# Sheet1.net
KiCad netlist of a schematic drawn in Altium Designer
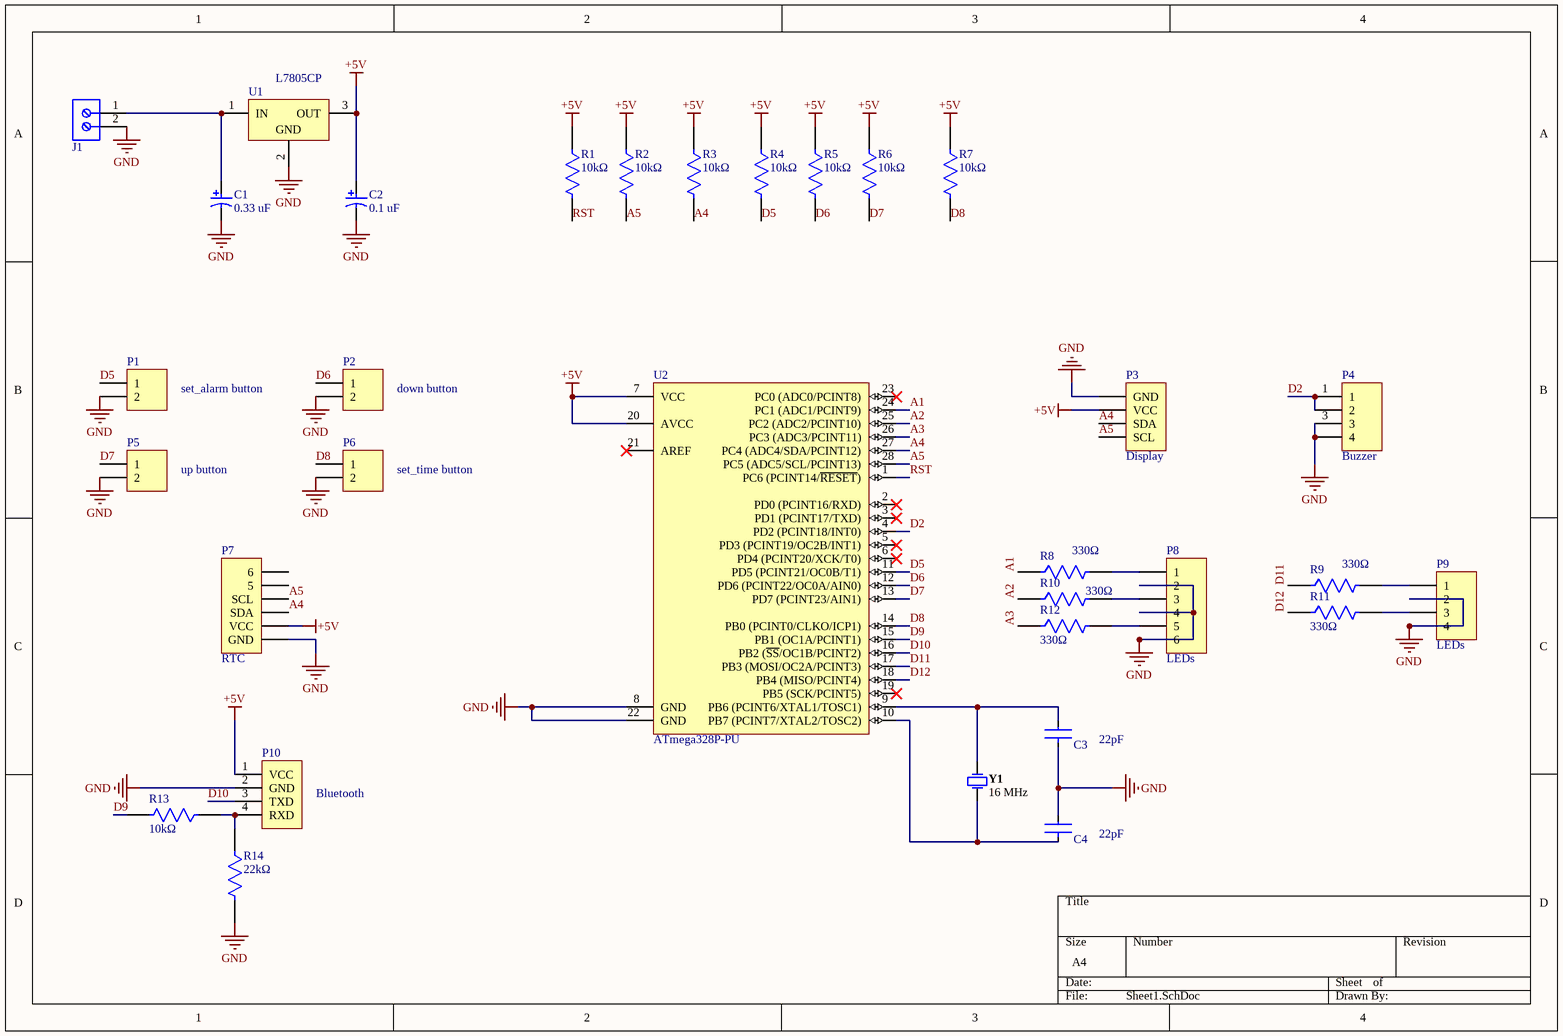
[diagram p0: Sheet1.SchDoc]

(export (version "E")
  (design (tool "Eeschema 10.0.6"))
  (components
    (comp (ref "C1")
      (value "PLF1A471MDO1_big")
      (footprint "NIC-PLF-10x13-2_V")
      (description "Aluminum Electrolytic Capacitor, 470 uF +/-20%, 10 V, -55 to 105 degC, 2-Pin THD, RoHS")
      (fields
        (field (name "RATED CAPACITANCE") "0.33 uF")
        (field (name "MANUFACTURER") "Nichicon")
        (field (name "PARTNUMBER") "PLF1A471MDO1")
      )
      (libsource (lib "Altium Content Vault") (part "NIC-CAP-P-2"))
    )
    (comp (ref "C2")
      (value "PLF1A471MDO1_big")
      (footprint "NIC-PLF-10x13-2_V")
      (description "Aluminum Electrolytic Capacitor, 470 uF +/-20%, 10 V, -55 to 105 degC, 2-Pin THD, RoHS")
      (fields
        (field (name "RATED CAPACITANCE") "0.1 uF")
        (field (name "MANUFACTURER") "Nichicon")
        (field (name "PARTNUMBER") "PLF1A471MDO1")
      )
      (libsource (lib "Altium Content Vault") (part "NIC-CAP-P-2"))
    )
    (comp (ref "C3")
      (value "RDE5C1H220J0K1H03B")
      (footprint "FP-RDE0M1-MFG")
      (description "Ceramic Capacitor 22pF ±5% 50V C0G Radial")
      (fields (field (name "CAPACITANCE") "22pF") (field (name "TOLERANCE") "5%"))
      (libsource (lib "Altium Content Vault") (part "b4654b650e69147ec39a6b967a45e02"))
    )
    (comp (ref "C4")
      (value "RDE5C1H220J0K1H03B")
      (footprint "FP-RDE0M1-MFG")
      (description "Ceramic Capacitor 22pF ±5% 50V C0G Radial")
      (fields (field (name "CAPACITANCE") "22pF") (field (name "TOLERANCE") "5%"))
      (libsource (lib "Altium Content Vault") (part "b4654b650e69147ec39a6b967a45e02"))
    )
    (comp (ref "J1")
      (value "691102710002")
      (footprint "691102710002")
      (description "Series 102 - 5.00 mm Horizontal Entry Modular with Pressure Clamp WR-TBL, 2 pin")
      (fields (field (name "MANUFACTURER") "Wurth Elektronik") (field (name "PUBLISHER") "WurthElektronik"))
      (libsource (lib "Altium Content Vault") (part "WE-CN-1P-F-TB2"))
    )
    (comp (ref "P1")
      (value "set_alarm button")
      (footprint "HDR1X2")
      (description "Header, 2-Pin")
      (fields (field (name "PUBLISHER") "Altium Limited"))
      (libsource (lib "Miscellaneous Connectors") (part "Header 2"))
    )
    (comp (ref "P2")
      (value "down button")
      (footprint "HDR1X2")
      (description "Header, 2-Pin")
      (fields (field (name "PUBLISHER") "Altium Limited"))
      (libsource (lib "Miscellaneous Connectors") (part "Header 2"))
    )
    (comp (ref "P3")
      (value "Display")
      (footprint "HDR1X4")
      (description "Header, 4-Pin")
      (fields (field (name "PUBLISHER") "Altium Limited"))
      (libsource (lib "Miscellaneous Connectors") (part "Header 4"))
    )
    (comp (ref "P4")
      (value "Buzzer")
      (footprint "HDR1X4")
      (description "Header, 4-Pin")
      (fields (field (name "PUBLISHER") "Altium Limited"))
      (libsource (lib "") (part "Header 4_2"))
    )
    (comp (ref "P5")
      (value "up button")
      (footprint "HDR1X2")
      (description "Header, 2-Pin")
      (fields (field (name "PUBLISHER") "Altium Limited"))
      (libsource (lib "Miscellaneous Connectors") (part "Header 2"))
    )
    (comp (ref "P6")
      (value "set_time button")
      (footprint "HDR1X2")
      (description "Header, 2-Pin")
      (fields (field (name "PUBLISHER") "Altium Limited"))
      (libsource (lib "Miscellaneous Connectors") (part "Header 2"))
    )
    (comp (ref "P7")
      (value "RTC")
      (footprint "HDR1X6")
      (description "Header, 6-Pin")
      (fields (field (name "PUBLISHER") "Altium Limited"))
      (libsource (lib "") (part "Header 6_1"))
    )
    (comp (ref "P8")
      (value "LEDs")
      (footprint "HDR1X6")
      (description "Header, 6-Pin")
      (fields (field (name "PUBLISHER") "Altium Limited"))
      (libsource (lib "Miscellaneous Connectors") (part "Header 6"))
    )
    (comp (ref "P9")
      (value "LEDs")
      (footprint "HDR1X4")
      (description "Header, 4-Pin")
      (fields (field (name "PUBLISHER") "Altium Limited"))
      (libsource (lib "Miscellaneous Connectors") (part "Header 4"))
    )
    (comp (ref "P10")
      (value "Bluetooth")
      (footprint "HDR1X4")
      (description "Header, 4-Pin")
      (fields (field (name "PUBLISHER") "Altium Limited"))
      (libsource (lib "") (part "Header 4_1"))
    )
    (comp (ref "R1")
      (value "MFR-25FBF52-1K18")
      (footprint "FP-MFR-25-MFG")
      (description "RES 1.18K OHM 1/4W 1% AXIAL")
      (fields
        (field (name "MANUFACTURER") "Yageo")
        (field (name "TOLERANCE") "1%")
        (field (name "RESISTANCE") "10kΩ")
      )
      (libsource (lib "Altium Content Vault") (part "1029c3af85768c4190bb7ad29bc67b5"))
    )
    (comp (ref "R2")
      (value "MFR-25FBF52-1K18")
      (footprint "FP-MFR-25-MFG")
      (description "RES 1.18K OHM 1/4W 1% AXIAL")
      (fields
        (field (name "MANUFACTURER") "Yageo")
        (field (name "TOLERANCE") "1%")
        (field (name "RESISTANCE") "10kΩ")
      )
      (libsource (lib "Altium Content Vault") (part "1029c3af85768c4190bb7ad29bc67b5"))
    )
    (comp (ref "R3")
      (value "MFR-25FBF52-1K18")
      (footprint "FP-MFR-25-MFG")
      (description "RES 1.18K OHM 1/4W 1% AXIAL")
      (fields
        (field (name "MANUFACTURER") "Yageo")
        (field (name "TOLERANCE") "1%")
        (field (name "RESISTANCE") "10kΩ")
      )
      (libsource (lib "Altium Content Vault") (part "1029c3af85768c4190bb7ad29bc67b5"))
    )
    (comp (ref "R4")
      (value "MFR-25FBF52-1K18")
      (footprint "FP-MFR-25-MFG")
      (description "RES 1.18K OHM 1/4W 1% AXIAL")
      (fields
        (field (name "MANUFACTURER") "Yageo")
        (field (name "TOLERANCE") "1%")
        (field (name "RESISTANCE") "10kΩ")
      )
      (libsource (lib "Altium Content Vault") (part "1029c3af85768c4190bb7ad29bc67b5"))
    )
    (comp (ref "R5")
      (value "MFR-25FBF52-1K18")
      (footprint "FP-MFR-25-MFG")
      (description "RES 1.18K OHM 1/4W 1% AXIAL")
      (fields
        (field (name "MANUFACTURER") "Yageo")
        (field (name "TOLERANCE") "1%")
        (field (name "RESISTANCE") "10kΩ")
      )
      (libsource (lib "Altium Content Vault") (part "1029c3af85768c4190bb7ad29bc67b5"))
    )
    (comp (ref "R6")
      (value "MFR-25FBF52-1K18")
      (footprint "FP-MFR-25-MFG")
      (description "RES 1.18K OHM 1/4W 1% AXIAL")
      (fields
        (field (name "MANUFACTURER") "Yageo")
        (field (name "TOLERANCE") "1%")
        (field (name "RESISTANCE") "10kΩ")
      )
      (libsource (lib "Altium Content Vault") (part "1029c3af85768c4190bb7ad29bc67b5"))
    )
    (comp (ref "R7")
      (value "MFR-25FBF52-1K18")
      (footprint "FP-MFR-25-MFG")
      (description "RES 1.18K OHM 1/4W 1% AXIAL")
      (fields
        (field (name "MANUFACTURER") "Yageo")
        (field (name "TOLERANCE") "1%")
        (field (name "RESISTANCE") "10kΩ")
      )
      (libsource (lib "Altium Content Vault") (part "1029c3af85768c4190bb7ad29bc67b5"))
    )
    (comp (ref "R8")
      (value "MFR-25FBF52-1K18")
      (footprint "FP-MFR-25-MFG")
      (description "RES 1.18K OHM 1/4W 1% AXIAL")
      (fields
        (field (name "MANUFACTURER") "Yageo")
        (field (name "TOLERANCE") "1%")
        (field (name "RESISTANCE") "330Ω")
      )
      (libsource (lib "Altium Content Vault") (part "1029c3af85768c4190bb7ad29bc67b5"))
    )
    (comp (ref "R9")
      (value "MFR-25FBF52-1K18")
      (footprint "FP-MFR-25-MFG")
      (description "RES 1.18K OHM 1/4W 1% AXIAL")
      (fields
        (field (name "MANUFACTURER") "Yageo")
        (field (name "TOLERANCE") "1%")
        (field (name "RESISTANCE") "330Ω")
      )
      (libsource (lib "Altium Content Vault") (part "1029c3af85768c4190bb7ad29bc67b5"))
    )
    (comp (ref "R10")
      (value "MFR-25FBF52-1K18")
      (footprint "FP-MFR-25-MFG")
      (description "RES 1.18K OHM 1/4W 1% AXIAL")
      (fields
        (field (name "MANUFACTURER") "Yageo")
        (field (name "TOLERANCE") "1%")
        (field (name "RESISTANCE") "330Ω")
      )
      (libsource (lib "Altium Content Vault") (part "1029c3af85768c4190bb7ad29bc67b5"))
    )
    (comp (ref "R11")
      (value "MFR-25FBF52-1K18")
      (footprint "FP-MFR-25-MFG")
      (description "RES 1.18K OHM 1/4W 1% AXIAL")
      (fields
        (field (name "MANUFACTURER") "Yageo")
        (field (name "TOLERANCE") "1%")
        (field (name "RESISTANCE") "330Ω")
      )
      (libsource (lib "Altium Content Vault") (part "1029c3af85768c4190bb7ad29bc67b5"))
    )
    (comp (ref "R12")
      (value "MFR-25FBF52-1K18")
      (footprint "FP-MFR-25-MFG")
      (description "RES 1.18K OHM 1/4W 1% AXIAL")
      (fields
        (field (name "MANUFACTURER") "Yageo")
        (field (name "TOLERANCE") "1%")
        (field (name "RESISTANCE") "330Ω")
      )
      (libsource (lib "Altium Content Vault") (part "1029c3af85768c4190bb7ad29bc67b5"))
    )
    (comp (ref "R13")
      (value "MFR-25FBF52-1K18")
      (footprint "FP-MFR-25-MFG")
      (description "RES 1.18K OHM 1/4W 1% AXIAL")
      (fields
        (field (name "MANUFACTURER") "Yageo")
        (field (name "TOLERANCE") "1%")
        (field (name "RESISTANCE") "10kΩ")
      )
      (libsource (lib "Altium Content Vault") (part "1029c3af85768c4190bb7ad29bc67b5"))
    )
    (comp (ref "R14")
      (value "MFR-25FBF52-1K18")
      (footprint "FP-MFR-25-MFG")
      (description "RES 1.18K OHM 1/4W 1% AXIAL")
      (fields
        (field (name "MANUFACTURER") "Yageo")
        (field (name "TOLERANCE") "1%")
        (field (name "RESISTANCE") "22kΩ")
      )
      (libsource (lib "Altium Content Vault") (part "1029c3af85768c4190bb7ad29bc67b5"))
    )
    (comp (ref "U1")
      (value "L7805CP")
      (footprint "TO220FP")
      (description "Positive Voltage Regulator, 5V, 3-Pin TO-220FP")
      (libsource (lib "Altium Content Vault") (part "PM-REG-L4940-SIL3"))
    )
    (comp (ref "U2")
      (value "ATmega328P-PU")
      (footprint "28P3")
      (libsource (lib "Altium Content Vault") (part "MC-8B-ATM48-IL28"))
    )
    (comp (ref "Y1")
      (value "16 MHz")
      (footprint "FOX-FOXSLF160-20")
      (description "Resistance Weld Thru-Hole Crystal, 16 MHz, -20 to 70 degC, 2-Pin THD, RoHS, Bulk")
      (fields (field (name "TOLERANCE") "1%"))
      (libsource (lib "Altium Content Vault") (part "XTAL-1-2-2"))
    )
  )
  (nets
    (net (code "1") (name "+5V") (class "Default")
      (node (ref "C2") (pin "1") (pinfunction "1_1") (pintype "passive"))
      (node (ref "P10") (pin "1") (pinfunction "VCC_1") (pintype "passive"))
      (node (ref "P3") (pin "2") (pinfunction "VCC_2") (pintype "passive"))
      (node (ref "P7") (pin "2") (pinfunction "VCC_2") (pintype "passive"))
      (node (ref "R1") (pin "1") (pinfunction "1_1") (pintype "passive"))
      (node (ref "R2") (pin "1") (pinfunction "1_1") (pintype "passive"))
      (node (ref "R3") (pin "1") (pinfunction "1_1") (pintype "passive"))
      (node (ref "R4") (pin "1") (pinfunction "1_1") (pintype "passive"))
      (node (ref "R5") (pin "1") (pinfunction "1_1") (pintype "passive"))
      (node (ref "R6") (pin "1") (pinfunction "1_1") (pintype "passive"))
      (node (ref "R7") (pin "1") (pinfunction "1_1") (pintype "passive"))
      (node (ref "U1") (pin "3") (pinfunction "OUT_3") (pintype "power_in"))
      (node (ref "U2") (pin "20") (pinfunction "AVCC_20") (pintype "power_in"))
      (node (ref "U2") (pin "7") (pinfunction "VCC_7") (pintype "power_in"))
    )
    (net (code "2") (name "/A1") (class "Default")
      (node (ref "R8") (pin "1") (pinfunction "1_1") (pintype "passive"))
      (node (ref "U2") (pin "24") (pinfunction "PC1_(ADC1/PCINT9)_24") (pintype "bidirectional"))
    )
    (net (code "3") (name "/A2") (class "Default")
      (node (ref "R10") (pin "1") (pinfunction "1_1") (pintype "passive"))
      (node (ref "U2") (pin "25") (pinfunction "PC2_(ADC2/PCINT10)_25") (pintype "bidirectional"))
    )
    (net (code "4") (name "/A3") (class "Default")
      (node (ref "R12") (pin "1") (pinfunction "1_1") (pintype "passive"))
      (node (ref "U2") (pin "26") (pinfunction "PC3_(ADC3/PCINT11)_26") (pintype "bidirectional"))
    )
    (net (code "5") (name "/A4") (class "Default")
      (node (ref "P3") (pin "3") (pinfunction "SDA_3") (pintype "passive"))
      (node (ref "P7") (pin "3") (pinfunction "SDA_3") (pintype "passive"))
      (node (ref "R3") (pin "2") (pinfunction "2_2") (pintype "passive"))
      (node (ref "U2") (pin "27") (pinfunction "PC4_(ADC4/SDA/PCINT12)_27") (pintype "bidirectional"))
    )
    (net (code "6") (name "/A5") (class "Default")
      (node (ref "P3") (pin "4") (pinfunction "SCL_4") (pintype "passive"))
      (node (ref "P7") (pin "4") (pinfunction "SCL_4") (pintype "passive"))
      (node (ref "R2") (pin "2") (pinfunction "2_2") (pintype "passive"))
      (node (ref "U2") (pin "28") (pinfunction "PC5_(ADC5/SCL/PCINT13)_28") (pintype "bidirectional"))
    )
    (net (code "7") (name "/D2") (class "Default")
      (node (ref "P4") (pin "1") (pinfunction "1_1") (pintype "passive"))
      (node (ref "P4") (pin "2") (pinfunction "2_2") (pintype "passive"))
      (node (ref "U2") (pin "4") (pinfunction "PD2_(PCINT18/INT0)_4") (pintype "bidirectional"))
    )
    (net (code "8") (name "/D5") (class "Default")
      (node (ref "P1") (pin "1") (pinfunction "1_1") (pintype "passive"))
      (node (ref "R4") (pin "2") (pinfunction "2_2") (pintype "passive"))
      (node (ref "U2") (pin "11") (pinfunction "PD5_(PCINT21/OC0B/T1)_11") (pintype "bidirectional"))
    )
    (net (code "9") (name "/D6") (class "Default")
      (node (ref "P2") (pin "1") (pinfunction "1_1") (pintype "passive"))
      (node (ref "R5") (pin "2") (pinfunction "2_2") (pintype "passive"))
      (node (ref "U2") (pin "12") (pinfunction "PD6_(PCINT22/OC0A/AIN0)_12") (pintype "bidirectional"))
    )
    (net (code "10") (name "/D7") (class "Default")
      (node (ref "P5") (pin "1") (pinfunction "1_1") (pintype "passive"))
      (node (ref "R6") (pin "2") (pinfunction "2_2") (pintype "passive"))
      (node (ref "U2") (pin "13") (pinfunction "PD7_(PCINT23/AIN1)_13") (pintype "bidirectional"))
    )
    (net (code "11") (name "/D8") (class "Default")
      (node (ref "P6") (pin "1") (pinfunction "1_1") (pintype "passive"))
      (node (ref "R7") (pin "2") (pinfunction "2_2") (pintype "passive"))
      (node (ref "U2") (pin "14") (pinfunction "PB0_(PCINT0/CLKO/ICP1)_14") (pintype "bidirectional"))
    )
    (net (code "12") (name "/D9") (class "Default")
      (node (ref "R13") (pin "2") (pinfunction "2_2") (pintype "passive"))
      (node (ref "U2") (pin "15") (pinfunction "PB1_(OC1A/PCINT1)_15") (pintype "bidirectional"))
    )
    (net (code "13") (name "/D10") (class "Default")
      (node (ref "P10") (pin "3") (pinfunction "TXD_3") (pintype "passive"))
      (node (ref "U2") (pin "16") (pinfunction "PB2_(~{SS}/OC1B/PCINT2)_16") (pintype "bidirectional"))
    )
    (net (code "14") (name "/D11") (class "Default")
      (node (ref "R9") (pin "1") (pinfunction "1_1") (pintype "passive"))
      (node (ref "U2") (pin "17") (pinfunction "PB3_(MOSI/OC2A/PCINT3)_17") (pintype "bidirectional"))
    )
    (net (code "15") (name "/D12") (class "Default")
      (node (ref "R11") (pin "1") (pinfunction "1_1") (pintype "passive"))
      (node (ref "U2") (pin "18") (pinfunction "PB4_(MISO/PCINT4)_18") (pintype "bidirectional"))
    )
    (net (code "16") (name "/RST") (class "Default")
      (node (ref "R1") (pin "2") (pinfunction "2_2") (pintype "passive"))
      (node (ref "U2") (pin "1") (pinfunction "PC6_(PCINT14/~{RESET})_1") (pintype "bidirectional"))
    )
    (net (code "17") (name "GND") (class "Default")
      (node (ref "C1") (pin "2") (pinfunction "2_2") (pintype "passive"))
      (node (ref "C2") (pin "2") (pinfunction "2_2") (pintype "passive"))
      (node (ref "C3") (pin "1") (pinfunction "1_1") (pintype "passive"))
      (node (ref "C4") (pin "2") (pinfunction "2_2") (pintype "passive"))
      (node (ref "J1") (pin "2") (pinfunction "2_2") (pintype "passive"))
      (node (ref "P1") (pin "2") (pinfunction "2_2") (pintype "passive"))
      (node (ref "P10") (pin "2") (pinfunction "GND_2") (pintype "passive"))
      (node (ref "P2") (pin "2") (pinfunction "2_2") (pintype "passive"))
      (node (ref "P3") (pin "1") (pinfunction "GND_1") (pintype "passive"))
      (node (ref "P4") (pin "3") (pinfunction "3_3") (pintype "passive"))
      (node (ref "P4") (pin "4") (pinfunction "4_4") (pintype "passive"))
      (node (ref "P5") (pin "2") (pinfunction "2_2") (pintype "passive"))
      (node (ref "P6") (pin "2") (pinfunction "2_2") (pintype "passive"))
      (node (ref "P7") (pin "1") (pinfunction "GND_1") (pintype "passive"))
      (node (ref "P8") (pin "2") (pinfunction "2_2") (pintype "passive"))
      (node (ref "P8") (pin "4") (pinfunction "4_4") (pintype "passive"))
      (node (ref "P8") (pin "6") (pinfunction "6_6") (pintype "passive"))
      (node (ref "P9") (pin "2") (pinfunction "VCC_2") (pintype "passive"))
      (node (ref "P9") (pin "4") (pinfunction "SCL_4") (pintype "passive"))
      (node (ref "R14") (pin "2") (pinfunction "2_2") (pintype "passive"))
      (node (ref "U1") (pin "2") (pinfunction "GND_2") (pintype "power_in"))
      (node (ref "U2") (pin "22") (pinfunction "GND_22") (pintype "power_in"))
      (node (ref "U2") (pin "8") (pinfunction "GND_8") (pintype "power_in"))
    )
    (net (code "18") (name "Net-(P8-Pad1)") (class "Default")
      (node (ref "P8") (pin "1") (pinfunction "1_1") (pintype "passive"))
      (node (ref "R8") (pin "2") (pinfunction "2_2") (pintype "passive"))
    )
    (net (code "19") (name "Net-(P8-Pad3)") (class "Default")
      (node (ref "P8") (pin "3") (pinfunction "3_3") (pintype "passive"))
      (node (ref "R10") (pin "2") (pinfunction "2_2") (pintype "passive"))
    )
    (net (code "20") (name "Net-(P8-Pad5)") (class "Default")
      (node (ref "P8") (pin "5") (pinfunction "5_5") (pintype "passive"))
      (node (ref "R12") (pin "2") (pinfunction "2_2") (pintype "passive"))
    )
    (net (code "21") (name "Net-(P9-GND)") (class "Default")
      (node (ref "P9") (pin "1") (pinfunction "GND_1") (pintype "passive"))
      (node (ref "R9") (pin "2") (pinfunction "2_2") (pintype "passive"))
    )
    (net (code "22") (name "Net-(P9-SDA)") (class "Default")
      (node (ref "P9") (pin "3") (pinfunction "SDA_3") (pintype "passive"))
      (node (ref "R11") (pin "2") (pinfunction "2_2") (pintype "passive"))
    )
    (net (code "23") (name "Net-(P10-RXD)") (class "Default")
      (node (ref "P10") (pin "4") (pinfunction "RXD_4") (pintype "passive"))
      (node (ref "R13") (pin "1") (pinfunction "1_1") (pintype "passive"))
      (node (ref "R14") (pin "1") (pinfunction "1_1") (pintype "passive"))
    )
    (net (code "24") (name "Net-(U1-IN)") (class "Default")
      (node (ref "C1") (pin "1") (pinfunction "1_1") (pintype "passive"))
      (node (ref "J1") (pin "1") (pinfunction "1_1") (pintype "passive"))
      (node (ref "U1") (pin "1") (pinfunction "IN_1") (pintype "power_in"))
    )
    (net (code "25") (name "Net-(U2-PB6_(PCINT6{slash}XTAL1{slash}TOSC1))") (class "Default")
      (node (ref "C3") (pin "2") (pinfunction "2_2") (pintype "passive"))
      (node (ref "U2") (pin "9") (pinfunction "PB6_(PCINT6/XTAL1/TOSC1)_9") (pintype "bidirectional"))
      (node (ref "Y1") (pin "1") (pinfunction "1_1") (pintype "passive"))
    )
    (net (code "26") (name "Net-(U2-PB7_(PCINT7{slash}XTAL2{slash}TOSC2))") (class "Default")
      (node (ref "C4") (pin "1") (pinfunction "1_1") (pintype "passive"))
      (node (ref "U2") (pin "10") (pinfunction "PB7_(PCINT7/XTAL2/TOSC2)_10") (pintype "bidirectional"))
      (node (ref "Y1") (pin "2") (pinfunction "2_2") (pintype "passive"))
    )
    (net (code "27") (name "unconnected-(P7-Pad5)") (class "Default")
      (node (ref "P7") (pin "5") (pinfunction "5_5") (pintype "passive"))
    )
    (net (code "28") (name "unconnected-(P7-Pad6)") (class "Default")
      (node (ref "P7") (pin "6") (pinfunction "6_6") (pintype "passive"))
    )
    (net (code "29") (name "unconnected-(U2-AREF-Pad21)") (class "Default")
      (node (ref "U2") (pin "21") (pinfunction "AREF_21") (pintype "power_in+no_connect"))
    )
    (net (code "30") (name "unconnected-(U2-PB5_(SCK{slash}PCINT5)-Pad19)") (class "Default")
      (node (ref "U2") (pin "19") (pinfunction "PB5_(SCK/PCINT5)_19") (pintype "bidirectional+no_connect"))
    )
    (net (code "31") (name "unconnected-(U2-PC0_(ADC0{slash}PCINT8)-Pad23)") (class "Default")
      (node (ref "U2") (pin "23") (pinfunction "PC0_(ADC0/PCINT8)_23") (pintype "bidirectional+no_connect"))
    )
    (net (code "32") (name "unconnected-(U2-PD0_(PCINT16{slash}RXD)-Pad2)") (class "Default")
      (node (ref "U2") (pin "2") (pinfunction "PD0_(PCINT16/RXD)_2") (pintype "bidirectional+no_connect"))
    )
    (net (code "33") (name "unconnected-(U2-PD1_(PCINT17{slash}TXD)-Pad3)") (class "Default")
      (node (ref "U2") (pin "3") (pinfunction "PD1_(PCINT17/TXD)_3") (pintype "bidirectional+no_connect"))
    )
    (net (code "34") (name "unconnected-(U2-PD3_(PCINT19{slash}OC2B{slash}INT1)-Pad5)") (class "Default")
      (node (ref "U2") (pin "5") (pinfunction "PD3_(PCINT19/OC2B/INT1)_5") (pintype "bidirectional+no_connect"))
    )
    (net (code "35") (name "unconnected-(U2-PD4_(PCINT20{slash}XCK{slash}T0)-Pad6)") (class "Default")
      (node (ref "U2") (pin "6") (pinfunction "PD4_(PCINT20/XCK/T0)_6") (pintype "bidirectional+no_connect"))
    )
  )
)
